# mlx_dev_board.net
KiCad netlist of a schematic drawn in EAGLE
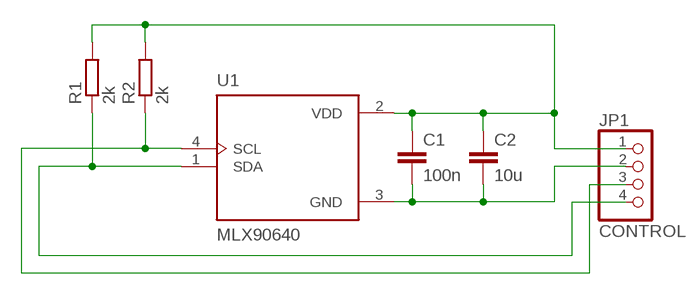
[diagram p0: schematic, sheet 1]

(export (version "E")
  (design (tool "Eeschema 10.0.6"))
  (components
    (comp (ref "C1")
      (value "100n")
      (footprint "eagle-import:C0805")
      (libsource (lib "eagle-import") (part "C-EUC0805"))
    )
    (comp (ref "C2")
      (value "10u")
      (footprint "eagle-import:C0805")
      (libsource (lib "eagle-import") (part "C-EUC0805"))
    )
    (comp (ref "JP1")
      (value "CONTROL")
      (footprint "eagle-import:1X04")
      (libsource (lib "eagle-import") (part "PINHD-1X4"))
    )
    (comp (ref "R1")
      (value "2k")
      (footprint "eagle-import:R0805")
      (libsource (lib "eagle-import") (part "R-EU_R0805"))
    )
    (comp (ref "R2")
      (value "2k")
      (footprint "eagle-import:R0805")
      (libsource (lib "eagle-import") (part "R-EU_R0805"))
    )
    (comp (ref "U1")
      (value "MLX90640")
      (footprint "eagle-import:TO292P945H1165-4")
      (fields (field (name "MF") "Melexis Technologies NV") (field (name "MP") "MLX90640ESF-BAB-000-TU"))
      (libsource (lib "eagle-import") (part "MLX90640ESF-BAB-000-TU"))
    )
  )
  (nets
    (net (code "1") (name "Net-(U1-GND)") (class "Default")
      (node (ref "C1") (pin "2") (pinfunction "2_2") (pintype "passive"))
      (node (ref "C2") (pin "2") (pinfunction "2_2") (pintype "passive"))
      (node (ref "JP1") (pin "2") (pinfunction "2_2") (pintype "passive"))
      (node (ref "U1") (pin "3") (pinfunction "GND_3") (pintype "power_in"))
    )
    (net (code "2") (name "Net-(U1-SCL)") (class "Default")
      (node (ref "JP1") (pin "3") (pinfunction "3_3") (pintype "passive"))
      (node (ref "R2") (pin "1") (pinfunction "1_1") (pintype "passive"))
      (node (ref "U1") (pin "4") (pinfunction "SCL_4") (pintype "input"))
    )
    (net (code "3") (name "Net-(U1-SDA)") (class "Default")
      (node (ref "JP1") (pin "4") (pinfunction "4_4") (pintype "passive"))
      (node (ref "R1") (pin "1") (pinfunction "1_1") (pintype "passive"))
      (node (ref "U1") (pin "1") (pinfunction "SDA_1") (pintype "bidirectional"))
    )
    (net (code "4") (name "Net-(U1-VDD)") (class "Default")
      (node (ref "C1") (pin "1") (pinfunction "1_1") (pintype "passive"))
      (node (ref "C2") (pin "1") (pinfunction "1_1") (pintype "passive"))
      (node (ref "JP1") (pin "1") (pinfunction "1_1") (pintype "passive"))
      (node (ref "R1") (pin "2") (pinfunction "2_2") (pintype "passive"))
      (node (ref "R2") (pin "2") (pinfunction "2_2") (pintype "passive"))
      (node (ref "U1") (pin "2") (pinfunction "VDD_2") (pintype "power_in"))
    )
  )
)
